# MCU_A_ESP32-WROOM-32U.net
KiCad netlist of a schematic drawn in Altium Designer
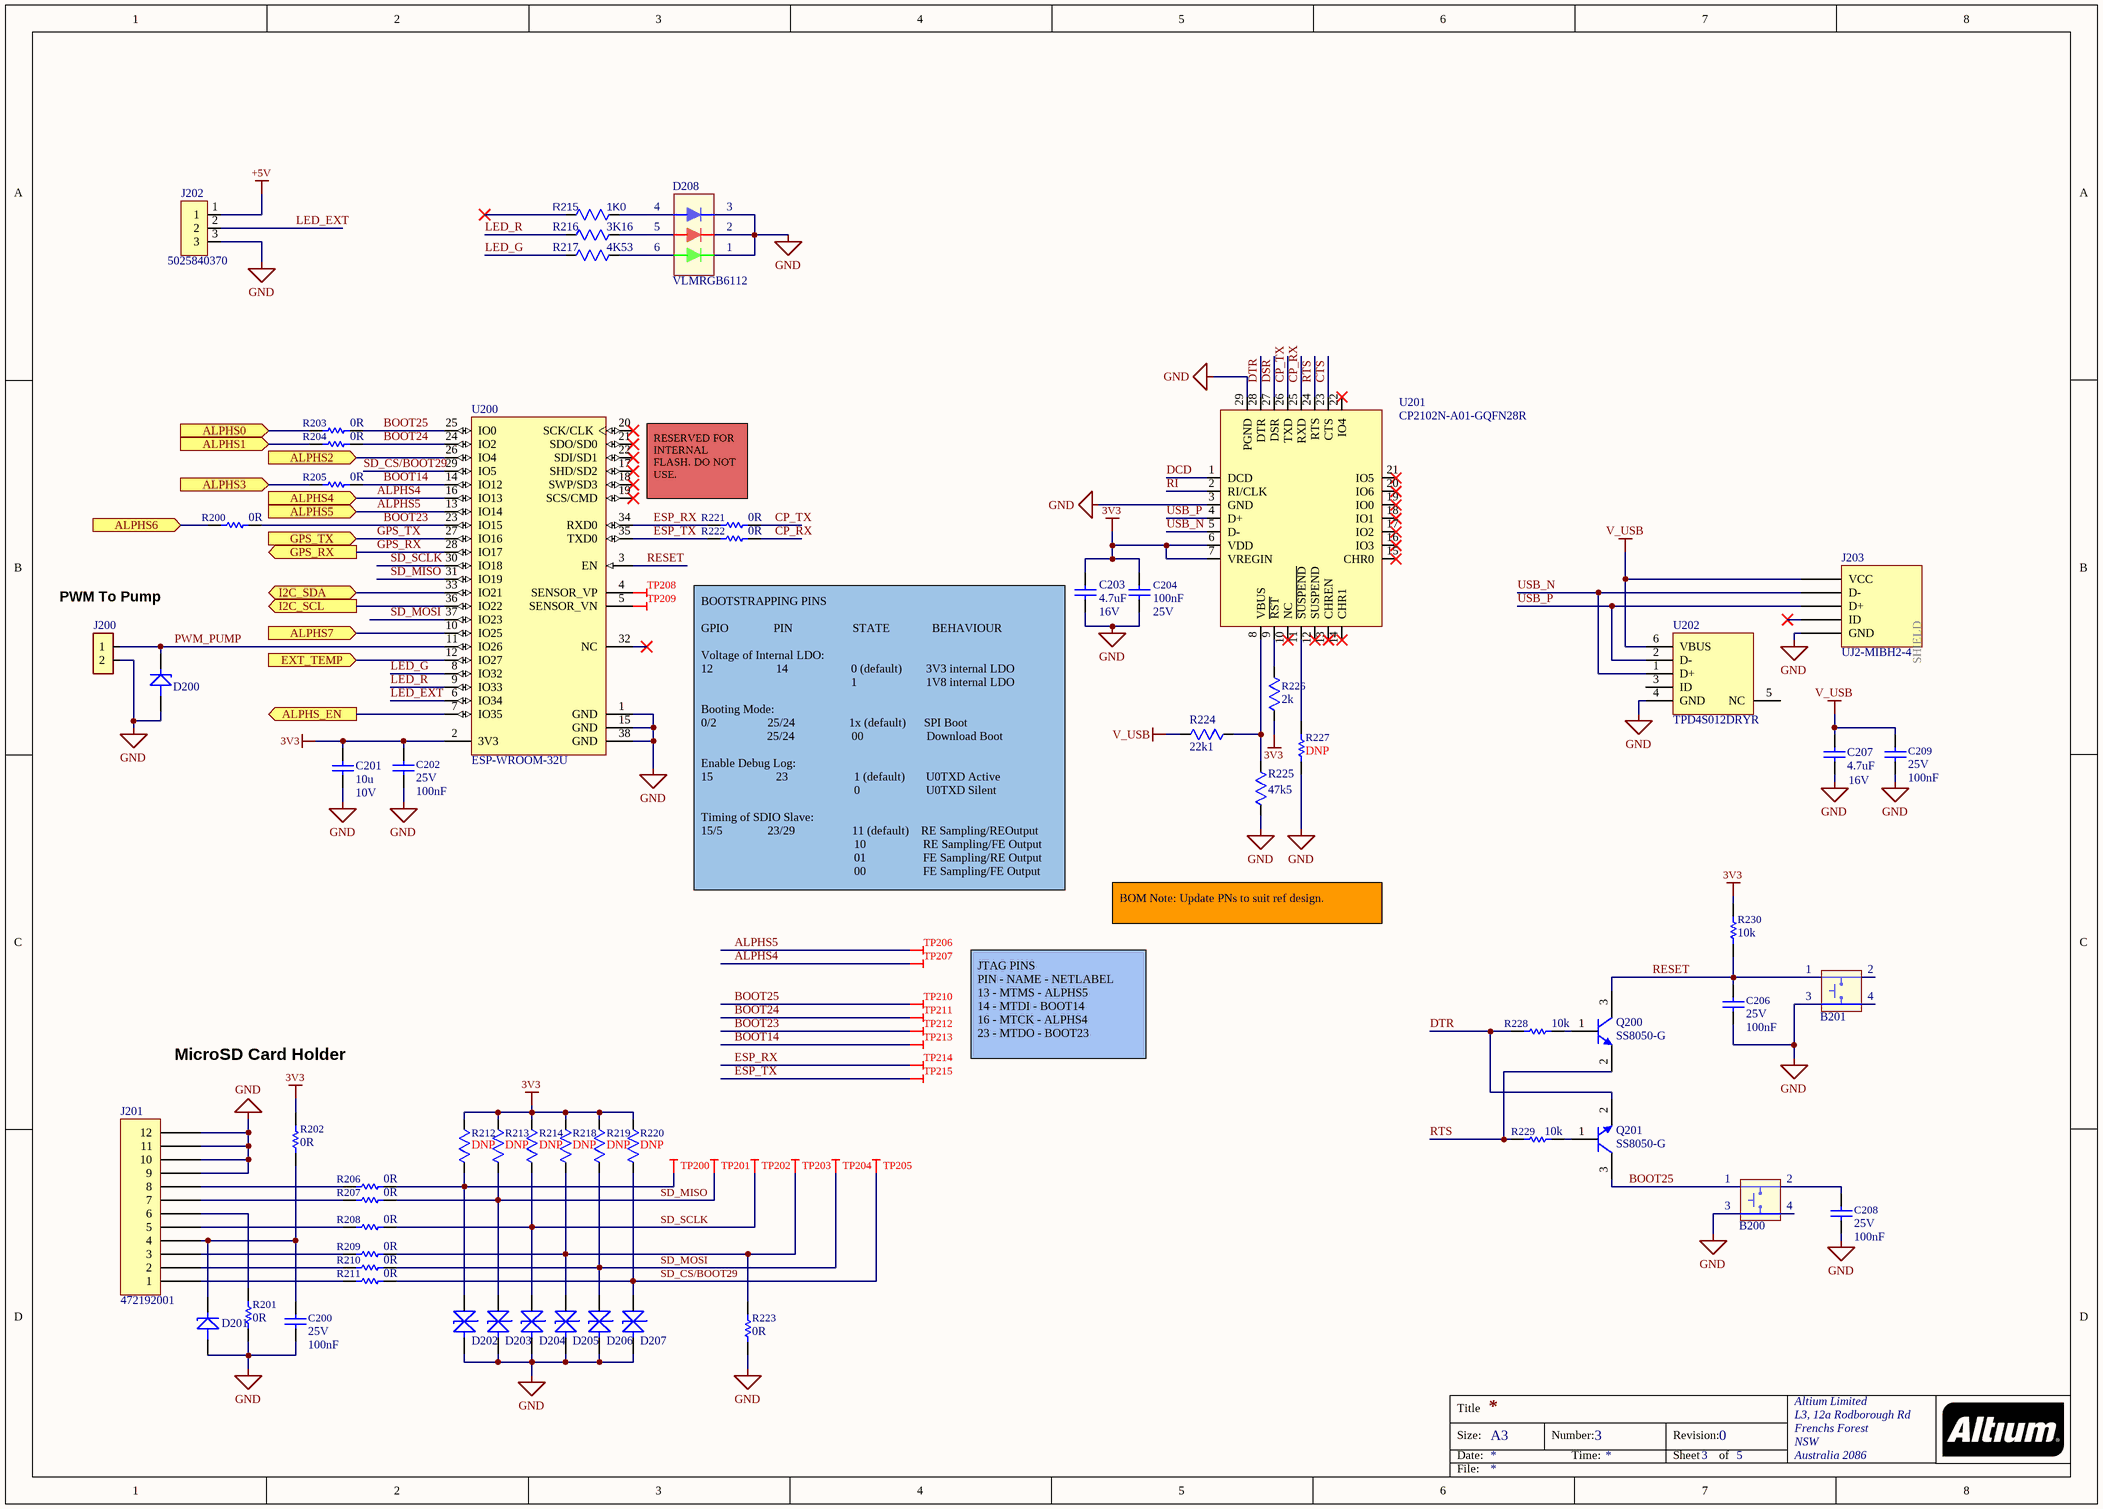
[diagram p0: MCU A ESP32-WROOM-32U.SchDoc]

(export (version "E")
  (design (tool "Eeschema 10.0.6"))
  (components
    (comp (ref "B200")
      (value "Button C&K PTS815 SJG 250 SMTR LFS")
      (footprint "PTS 815")
      (description "Push Button Top")
      (fields
        (field (name "MANUFACTURER") "C&K Components")
        (field (name "MANUFACTURER PART NUMBER") "PTS815 SJG 250 SMTR LFS")
      )
      (libsource (lib "Connectors") (part "Button C&K PTS815 SJG 250 SMTR LFS"))
    )
    (comp (ref "B201")
      (value "Button C&K PTS815 SJG 250 SMTR LFS")
      (footprint "PTS 815")
      (description "Push Button Top")
      (fields
        (field (name "MANUFACTURER") "C&K Components")
        (field (name "MANUFACTURER PART NUMBER") "PTS815 SJG 250 SMTR LFS")
      )
      (libsource (lib "Connectors") (part "Button C&K PTS815 SJG 250 SMTR LFS"))
    )
    (comp (ref "C200")
      (value "100nF")
      (footprint "CAPC1005X06N")
      (fields
        (field (name "VOLTAGE") "25V")
        (field (name "MANUFACTURER PART NUMBER") "CL05A104KA5NNNC")
        (field (name "MANUFACTURER") "Samsung")
        (field (name "Comment") "4.7uF")
      )
      (libsource (lib "Capacitors") (part "4.7uF_0603_10V"))
    )
    (comp (ref "C201")
      (value "10u")
      (footprint "CAPC1005X06N")
      (description "Capacitor")
      (fields
        (field (name "MANUFACTURER PART NUMBER") "CL05A106MP8NUB8")
        (field (name "MANUFACTURER") "Samsung")
        (field (name "VOLTAGE") "10V")
      )
      (libsource (lib "Santuary") (part "CAP{colon} GENERAL"))
    )
    (comp (ref "C202")
      (value "100nF")
      (footprint "CAPC1005X06N")
      (fields
        (field (name "VOLTAGE") "25V")
        (field (name "MANUFACTURER PART NUMBER") "CL05A104KA5NNNC")
        (field (name "MANUFACTURER") "Samsung")
        (field (name "Comment") "4.7uF")
      )
      (libsource (lib "Capacitors") (part "4.7uF_0603_10V"))
    )
    (comp (ref "C203")
      (value "4.7uF")
      (footprint "C1005[0402]")
      (description "Cap,4.7uF,10V,20%,X5R,0402")
      (fields
        (field (name "MANUFACTURER") "Samsung Electro-Mechanics")
        (field (name "MANUFACTURER PART NUMBER") "CL05A475MO5NUNC")
        (field (name "VOLTAGE") "16V")
      )
      (libsource (lib "Capacitors") (part "4.7uF_0402_10V"))
    )
    (comp (ref "C204")
      (value "100nF")
      (footprint "CAPC1005X06N")
      (fields
        (field (name "VOLTAGE") "25V")
        (field (name "MANUFACTURER PART NUMBER") "CL05A104KA5NNNC")
        (field (name "MANUFACTURER") "Samsung")
        (field (name "Comment") "4.7uF")
      )
      (libsource (lib "Capacitors") (part "4.7uF_0603_10V"))
    )
    (comp (ref "C206")
      (value "100nF")
      (footprint "CAPC1005X06N")
      (fields
        (field (name "VOLTAGE") "25V")
        (field (name "MANUFACTURER PART NUMBER") "CL05A104KA5NNNC")
        (field (name "MANUFACTURER") "Samsung")
        (field (name "Comment") "4.7uF")
      )
      (libsource (lib "Capacitors") (part "4.7uF_0603_10V"))
    )
    (comp (ref "C207")
      (value "4.7uF")
      (footprint "C1005[0402]")
      (description "Cap,4.7uF,10V,20%,X5R,0402")
      (fields
        (field (name "MANUFACTURER") "Samsung Electro-Mechanics")
        (field (name "MANUFACTURER PART NUMBER") "CL05A475MO5NUNC")
        (field (name "VOLTAGE") "16V")
      )
      (libsource (lib "Capacitors") (part "4.7uF_0402_10V"))
    )
    (comp (ref "C208")
      (value "100nF")
      (footprint "CAPC1005X06N")
      (fields
        (field (name "VOLTAGE") "25V")
        (field (name "MANUFACTURER PART NUMBER") "CL05A104KA5NNNC")
        (field (name "MANUFACTURER") "Samsung")
        (field (name "Comment") "4.7uF")
      )
      (libsource (lib "Capacitors") (part "4.7uF_0603_10V"))
    )
    (comp (ref "C209")
      (value "100nF")
      (footprint "CAPC1005X06N")
      (fields
        (field (name "VOLTAGE") "25V")
        (field (name "MANUFACTURER PART NUMBER") "CL05A104KA5NNNC")
        (field (name "MANUFACTURER") "Samsung")
        (field (name "Comment") "4.7uF")
      )
      (libsource (lib "Capacitors") (part "4.7uF_0603_10V"))
    )
    (comp (ref "D200")
      (value "3.3V TVS")
      (footprint "NXP PTVSxS1UR-Series (SOD123W)")
      (fields
        (field (name "MANUFACTURER") "Nexperia")
        (field (name "MANUFACTURER PART NUMBER") "PTVS3V3S1UTR,115")
      )
      (libsource (lib "FSM_2018") (part "NXP PTVSxS1UR-Series"))
    )
    (comp (ref "D201")
      (value "3.3V TVS")
      (footprint "NXP PTVSxS1UR-Series (SOD123W)")
      (fields
        (field (name "MANUFACTURER") "Nexperia")
        (field (name "MANUFACTURER PART NUMBER") "PTVS3V3S1UTR,115")
      )
      (libsource (lib "FSM_2018") (part "NXP PTVSxS1UR-Series"))
    )
    (comp (ref "D202")
      (value "ESD7951ST5GOSCT-ND")
      (footprint "SODFL100X40-2N")
      (description "TVS Diode")
      (fields
        (field (name "MANUFACTURER PART NUMBER") "ESD7951ST5G")
        (field (name "MANUFACTURER") "ON Semiconductor")
      )
      (libsource (lib "Gas Monitor Components") (part "ESD7951S"))
    )
    (comp (ref "D203")
      (value "ESD7951ST5GOSCT-ND")
      (footprint "SODFL100X40-2N")
      (description "TVS Diode")
      (fields
        (field (name "MANUFACTURER PART NUMBER") "ESD7951ST5G")
        (field (name "MANUFACTURER") "ON Semiconductor")
      )
      (libsource (lib "Gas Monitor Components") (part "ESD7951S"))
    )
    (comp (ref "D204")
      (value "ESD7951ST5GOSCT-ND")
      (footprint "SODFL100X40-2N")
      (description "TVS Diode")
      (fields
        (field (name "MANUFACTURER PART NUMBER") "ESD7951ST5G")
        (field (name "MANUFACTURER") "ON Semiconductor")
      )
      (libsource (lib "Gas Monitor Components") (part "ESD7951S"))
    )
    (comp (ref "D205")
      (value "ESD7951ST5GOSCT-ND")
      (footprint "SODFL100X40-2N")
      (description "TVS Diode")
      (fields
        (field (name "MANUFACTURER PART NUMBER") "ESD7951ST5G")
        (field (name "MANUFACTURER") "ON Semiconductor")
      )
      (libsource (lib "Gas Monitor Components") (part "ESD7951S"))
    )
    (comp (ref "D206")
      (value "ESD7951ST5GOSCT-ND")
      (footprint "SODFL100X40-2N")
      (description "TVS Diode")
      (fields
        (field (name "MANUFACTURER PART NUMBER") "ESD7951ST5G")
        (field (name "MANUFACTURER") "ON Semiconductor")
      )
      (libsource (lib "Gas Monitor Components") (part "ESD7951S"))
    )
    (comp (ref "D207")
      (value "ESD7951ST5GOSCT-ND")
      (footprint "SODFL100X40-2N")
      (description "TVS Diode")
      (fields
        (field (name "MANUFACTURER PART NUMBER") "ESD7951ST5G")
        (field (name "MANUFACTURER") "ON Semiconductor")
      )
      (libsource (lib "Gas Monitor Components") (part "ESD7951S"))
    )
    (comp (ref "D208")
      (value "VLMRGB6112")
      (footprint "VLMRGB6112")
      (description "LED RGB Clear 624nm/526nm/469nm 2V/3.1V/3V PLCC-6")
      (fields
        (field (name "MANUFACTURER") "Vishay Semiconductor Opto Division")
        (field (name "MANUFACTURER PART NUMBER") "VLMRGB6112-00-GS08")
      )
      (libsource (lib "LEDs") (part "VLMRGB6112"))
    )
    (comp (ref "J200")
      (value "PWM To Pump")
      (footprint "6410/2pin")
      (description "Connector 2 pin")
      (fields (field (name "MANUFACTURER") "Molex") (field (name "MANUFACTURER PART NUMBER") "0022232023"))
      (libsource (lib "VolcDB") (part "CON2"))
    )
    (comp (ref "J201")
      (value "472192001")
      (footprint "SD-47219-001")
      (fields (field (name "MANUFACTURER") "Molex") (field (name "MANUFACTURER PART NUMBER") "0472192001"))
      (libsource (lib "Gas Monitor Components") (part "CON12"))
    )
    (comp (ref "J202")
      (value "5025840370")
      (footprint "502584-0370")
      (fields (field (name "MANUFACTURER") "Molex"))
      (libsource (lib "Sora") (part "CONN{colon} 3x1"))
    )
    (comp (ref "J203")
      (value "UJ2-MIBH2-4")
      (footprint "UJ2-MIBH2-4-SMT")
      (fields
        (field (name "MANUFACTURER") "CUI")
        (field (name "MANUFACTURER PART NUMBER") "UJ2-MIBH2-4-SMT-TR")
      )
      (libsource (lib "Gas Monitor Components") (part "USB Shield"))
    )
    (comp (ref "Q200")
      (value "SS8050-G")
      (footprint "ONSC-SOT-23-3-318-08_V")
      (description "General Purpose Transistor, NPN Silicon, 3-Pin SOT-23, Tape and Reel")
      (fields (field (name "MANUFACTURER") "Comchip Technology"))
      (libsource (lib "Altium Content Vault") (part "ONSC-NPN-B1E2C3-3"))
    )
    (comp (ref "Q201")
      (value "SS8050-G")
      (footprint "ONSC-SOT-23-3-318-08_V")
      (description "General Purpose Transistor, NPN Silicon, 3-Pin SOT-23, Tape and Reel")
      (fields (field (name "MANUFACTURER") "Comchip Technology"))
      (libsource (lib "Altium Content Vault") (part "ONSC-NPN-B1E2C3-3"))
    )
    (comp (ref "R200")
      (value "0R")
      (footprint "RESC1005X03N")
      (fields
        (field (name "MANUFACTURER") "Panasonic")
        (field (name "MANUFACTURER PART NUMBER") "ERJ-2GE0R00X")
        (field (name "Comment") "RES: GENERAL")
      )
      (libsource (lib "Santuary") (part "RES{colon} GENERAL"))
    )
    (comp (ref "R201")
      (value "0R")
      (footprint "RESC1005X03N")
      (fields
        (field (name "MANUFACTURER") "Panasonic")
        (field (name "MANUFACTURER PART NUMBER") "ERJ-2GE0R00X")
        (field (name "Comment") "RES: GENERAL")
      )
      (libsource (lib "Santuary") (part "RES{colon} GENERAL"))
    )
    (comp (ref "R202")
      (value "0R")
      (footprint "RESC1005X03N")
      (fields
        (field (name "MANUFACTURER") "Panasonic")
        (field (name "MANUFACTURER PART NUMBER") "ERJ-2GE0R00X")
        (field (name "Comment") "RES: GENERAL")
      )
      (libsource (lib "Santuary") (part "RES{colon} GENERAL"))
    )
    (comp (ref "R203")
      (value "0R")
      (footprint "RESC1005X03N")
      (fields
        (field (name "MANUFACTURER") "Panasonic")
        (field (name "MANUFACTURER PART NUMBER") "ERJ-2GE0R00X")
        (field (name "Comment") "RES: GENERAL")
      )
      (libsource (lib "Santuary") (part "RES{colon} GENERAL"))
    )
    (comp (ref "R204")
      (value "0R")
      (footprint "RESC1005X03N")
      (fields
        (field (name "MANUFACTURER") "Panasonic")
        (field (name "MANUFACTURER PART NUMBER") "ERJ-2GE0R00X")
        (field (name "Comment") "RES: GENERAL")
      )
      (libsource (lib "Santuary") (part "RES{colon} GENERAL"))
    )
    (comp (ref "R205")
      (value "0R")
      (footprint "RESC1005X03N")
      (fields
        (field (name "MANUFACTURER") "Panasonic")
        (field (name "MANUFACTURER PART NUMBER") "ERJ-2GE0R00X")
        (field (name "Comment") "RES: GENERAL")
      )
      (libsource (lib "Santuary") (part "RES{colon} GENERAL"))
    )
    (comp (ref "R206")
      (value "0R")
      (footprint "RESC1005X03N")
      (fields
        (field (name "MANUFACTURER") "Panasonic")
        (field (name "MANUFACTURER PART NUMBER") "ERJ-2GE0R00X")
        (field (name "Comment") "RES: GENERAL")
      )
      (libsource (lib "Santuary") (part "RES{colon} GENERAL"))
    )
    (comp (ref "R207")
      (value "0R")
      (footprint "RESC1005X03N")
      (fields
        (field (name "MANUFACTURER") "Panasonic")
        (field (name "MANUFACTURER PART NUMBER") "ERJ-2GE0R00X")
        (field (name "Comment") "RES: GENERAL")
      )
      (libsource (lib "Santuary") (part "RES{colon} GENERAL"))
    )
    (comp (ref "R208")
      (value "0R")
      (footprint "RESC1005X03N")
      (fields
        (field (name "MANUFACTURER") "Panasonic")
        (field (name "MANUFACTURER PART NUMBER") "ERJ-2GE0R00X")
        (field (name "Comment") "RES: GENERAL")
      )
      (libsource (lib "Santuary") (part "RES{colon} GENERAL"))
    )
    (comp (ref "R209")
      (value "0R")
      (footprint "RESC1005X03N")
      (fields
        (field (name "MANUFACTURER") "Panasonic")
        (field (name "MANUFACTURER PART NUMBER") "ERJ-2GE0R00X")
        (field (name "Comment") "RES: GENERAL")
      )
      (libsource (lib "Santuary") (part "RES{colon} GENERAL"))
    )
    (comp (ref "R210")
      (value "0R")
      (footprint "RESC1005X03N")
      (fields
        (field (name "MANUFACTURER") "Panasonic")
        (field (name "MANUFACTURER PART NUMBER") "ERJ-2GE0R00X")
        (field (name "Comment") "RES: GENERAL")
      )
      (libsource (lib "Santuary") (part "RES{colon} GENERAL"))
    )
    (comp (ref "R211")
      (value "0R")
      (footprint "RESC1005X03N")
      (fields
        (field (name "MANUFACTURER") "Panasonic")
        (field (name "MANUFACTURER PART NUMBER") "ERJ-2GE0R00X")
        (field (name "Comment") "RES: GENERAL")
      )
      (libsource (lib "Santuary") (part "RES{colon} GENERAL"))
    )
    (comp (ref "R212")
      (value "DNP")
      (footprint "RESC1005X03N")
      (description "RES 1K Ohm ±5%, 0.25W,1/4W 0603")
      (fields (field (name "Comment") "10K"))
      (libsource (lib "Resistors") (part "1K00_0603_0.1W"))
    )
    (comp (ref "R213")
      (value "DNP")
      (footprint "RESC1005X03N")
      (description "RES 1K Ohm ±5%, 0.25W,1/4W 0603")
      (fields (field (name "Comment") "10K"))
      (libsource (lib "Resistors") (part "1K00_0603_0.1W"))
    )
    (comp (ref "R214")
      (value "DNP")
      (footprint "RESC1005X03N")
      (description "RES 1K Ohm ±5%, 0.25W,1/4W 0603")
      (fields (field (name "Comment") "10K"))
      (libsource (lib "Resistors") (part "1K00_0603_0.1W"))
    )
    (comp (ref "R215")
      (value "1K0")
      (footprint "R1608[0603] small")
      (description "RES 1K Ohm ±5%, 0.25W,1/4W 0603")
      (fields (field (name "MANUFACTURER") "Rohm") (field (name "MANUFACTURER PART NUMBER") "ESR03EZPJ102"))
      (libsource (lib "Resistors") (part "1K00_0603_0.1W"))
    )
    (comp (ref "R216")
      (value "3K16")
      (footprint "R1608[0603] small")
      (description "Res,SMD,1/10W,3K16,0603,1%")
      (fields
        (field (name "MANUFACTURER") "Stackpole Electronics")
        (field (name "MANUFACTURER PART NUMBER") "RMCF0603FT3K16")
      )
      (libsource (lib "Resistors") (part "3K16_Resistor_0603"))
    )
    (comp (ref "R217")
      (value "4K53")
      (footprint "R1608[0603] small")
      (description "Res,SMD,4K53,1/10W,1%,0603")
      (fields
        (field (name "MANUFACTURER") "Yageo")
        (field (name "MANUFACTURER PART NUMBER") "RC0603FR-074K53L")
      )
      (libsource (lib "Resistors") (part "4K53_Resistor_0603"))
    )
    (comp (ref "R218")
      (value "DNP")
      (footprint "RESC1005X03N")
      (description "RES 1K Ohm ±5%, 0.25W,1/4W 0603")
      (fields (field (name "Comment") "10K"))
      (libsource (lib "Resistors") (part "1K00_0603_0.1W"))
    )
    (comp (ref "R219")
      (value "DNP")
      (footprint "RESC1005X03N")
      (description "RES 1K Ohm ±5%, 0.25W,1/4W 0603")
      (fields (field (name "Comment") "10K"))
      (libsource (lib "Resistors") (part "1K00_0603_0.1W"))
    )
    (comp (ref "R220")
      (value "DNP")
      (footprint "RESC1005X03N")
      (description "RES 1K Ohm ±5%, 0.25W,1/4W 0603")
      (fields (field (name "Comment") "10K"))
      (libsource (lib "Resistors") (part "1K00_0603_0.1W"))
    )
    (comp (ref "R221")
      (value "0R")
      (footprint "RESC1005X03N")
      (fields
        (field (name "MANUFACTURER") "Panasonic")
        (field (name "MANUFACTURER PART NUMBER") "ERJ-2GE0R00X")
        (field (name "Comment") "RES: GENERAL")
      )
      (libsource (lib "Santuary") (part "RES{colon} GENERAL"))
    )
    (comp (ref "R222")
      (value "0R")
      (footprint "RESC1005X03N")
      (fields
        (field (name "MANUFACTURER") "Panasonic")
        (field (name "MANUFACTURER PART NUMBER") "ERJ-2GE0R00X")
        (field (name "Comment") "RES: GENERAL")
      )
      (libsource (lib "Santuary") (part "RES{colon} GENERAL"))
    )
    (comp (ref "R223")
      (value "0R")
      (footprint "RESC1005X03N")
      (fields
        (field (name "MANUFACTURER") "Panasonic")
        (field (name "MANUFACTURER PART NUMBER") "ERJ-2GE0R00X")
        (field (name "Comment") "RES: GENERAL")
      )
      (libsource (lib "Santuary") (part "RES{colon} GENERAL"))
    )
    (comp (ref "R224")
      (value "22k1")
      (footprint "R1005[0402]")
      (description "Res,SMD,22k,0603,5%,1/4W")
      (fields
        (field (name "MANUFACTURER PART NUMBER") "ERJ-2RKF2212X")
        (field (name "MANUFACTURER") "Panasonic")
      )
      (libsource (lib "Resistors") (part "22K_0603_1/4W"))
    )
    (comp (ref "R225")
      (value "47k5")
      (footprint "R1005[0402]")
      (description "Res,SMD,22k,0603,5%,1/4W")
      (fields
        (field (name "MANUFACTURER PART NUMBER") "ERJ-2RKF4752X")
        (field (name "MANUFACTURER") "Panasonic")
      )
      (libsource (lib "Resistors") (part "22K_0603_1/4W"))
    )
    (comp (ref "R226")
      (value "2k")
      (footprint "R1005[0402]")
      (fields
        (field (name "MANUFACTURER") "Panasonic")
        (field (name "MANUFACTURER PART NUMBER") "ERJ-2RKF2001X")
        (field (name "Comment") "10K")
      )
      (libsource (lib "Resistors") (part "1K00_0603_0.1W"))
    )
    (comp (ref "R227")
      (value "DNP")
      (footprint "RESC1005X03N")
      (fields (field (name "Comment") "RES: GENERAL"))
      (libsource (lib "Santuary") (part "RES{colon} GENERAL"))
    )
    (comp (ref "R228")
      (value "10k")
      (footprint "RESC1005X03N")
      (fields
        (field (name "MANUFACTURER") "Panasonic")
        (field (name "MANUFACTURER PART NUMBER") "ERJ-2RKF1002X")
        (field (name "Comment") "RES: GENERAL")
      )
      (libsource (lib "Santuary") (part "RES{colon} GENERAL"))
    )
    (comp (ref "R229")
      (value "10k")
      (footprint "RESC1005X03N")
      (fields
        (field (name "MANUFACTURER") "Panasonic")
        (field (name "MANUFACTURER PART NUMBER") "ERJ-2RKF1002X")
        (field (name "Comment") "RES: GENERAL")
      )
      (libsource (lib "Santuary") (part "RES{colon} GENERAL"))
    )
    (comp (ref "R230")
      (value "10k")
      (footprint "RESC1005X03N")
      (fields
        (field (name "MANUFACTURER") "Panasonic")
        (field (name "MANUFACTURER PART NUMBER") "ERJ-2RKF1002X")
        (field (name "Comment") "RES: GENERAL")
      )
      (libsource (lib "Santuary") (part "RES{colon} GENERAL"))
    )
    (comp (ref "TP200")
      (value "PAD")
      (footprint "TP_SMD_39MIL")
      (description "SMD Test Pad")
      (fields (field (name "MANUFACTURER") "No P/N Required"))
      (libsource (lib "Connectors") (part "TP_SMD_39MIL"))
    )
    (comp (ref "TP201")
      (value "PAD")
      (footprint "TP_SMD_39MIL")
      (description "SMD Test Pad")
      (fields (field (name "MANUFACTURER") "No P/N Required"))
      (libsource (lib "Connectors") (part "TP_SMD_39MIL"))
    )
    (comp (ref "TP202")
      (value "PAD")
      (footprint "TP_SMD_39MIL")
      (description "SMD Test Pad")
      (fields (field (name "MANUFACTURER") "No P/N Required"))
      (libsource (lib "Connectors") (part "TP_SMD_39MIL"))
    )
    (comp (ref "TP203")
      (value "PAD")
      (footprint "TP_SMD_39MIL")
      (description "SMD Test Pad")
      (fields (field (name "MANUFACTURER") "No P/N Required"))
      (libsource (lib "Connectors") (part "TP_SMD_39MIL"))
    )
    (comp (ref "TP204")
      (value "PAD")
      (footprint "TP_SMD_39MIL")
      (description "SMD Test Pad")
      (fields (field (name "MANUFACTURER") "No P/N Required"))
      (libsource (lib "Connectors") (part "TP_SMD_39MIL"))
    )
    (comp (ref "TP205")
      (value "PAD")
      (footprint "TP_SMD_39MIL")
      (description "SMD Test Pad")
      (fields (field (name "MANUFACTURER") "No P/N Required"))
      (libsource (lib "Connectors") (part "TP_SMD_39MIL"))
    )
    (comp (ref "TP206")
      (value "PAD")
      (footprint "TP_SMD_39MIL")
      (description "SMD Test Pad")
      (fields (field (name "MANUFACTURER") "No P/N Required"))
      (libsource (lib "Connectors") (part "TP_SMD_39MIL"))
    )
    (comp (ref "TP207")
      (value "PAD")
      (footprint "TP_SMD_39MIL")
      (description "SMD Test Pad")
      (fields (field (name "MANUFACTURER") "No P/N Required"))
      (libsource (lib "Connectors") (part "TP_SMD_39MIL"))
    )
    (comp (ref "TP208")
      (value "PAD")
      (footprint "TP_SMD_39MIL")
      (description "SMD Test Pad")
      (fields (field (name "MANUFACTURER") "No P/N Required"))
      (libsource (lib "Connectors") (part "TP_SMD_39MIL"))
    )
    (comp (ref "TP209")
      (value "PAD")
      (footprint "TP_SMD_39MIL")
      (description "SMD Test Pad")
      (fields (field (name "MANUFACTURER") "No P/N Required"))
      (libsource (lib "Connectors") (part "TP_SMD_39MIL"))
    )
    (comp (ref "TP210")
      (value "PAD")
      (footprint "TP_SMD_39MIL")
      (description "SMD Test Pad")
      (fields (field (name "MANUFACTURER") "No P/N Required"))
      (libsource (lib "Connectors") (part "TP_SMD_39MIL"))
    )
    (comp (ref "TP211")
      (value "PAD")
      (footprint "TP_SMD_39MIL")
      (description "SMD Test Pad")
      (fields (field (name "MANUFACTURER") "No P/N Required"))
      (libsource (lib "Connectors") (part "TP_SMD_39MIL"))
    )
    (comp (ref "TP212")
      (value "PAD")
      (footprint "TP_SMD_39MIL")
      (description "SMD Test Pad")
      (fields (field (name "MANUFACTURER") "No P/N Required"))
      (libsource (lib "Connectors") (part "TP_SMD_39MIL"))
    )
    (comp (ref "TP213")
      (value "PAD")
      (footprint "TP_SMD_39MIL")
      (description "SMD Test Pad")
      (fields (field (name "MANUFACTURER") "No P/N Required"))
      (libsource (lib "Connectors") (part "TP_SMD_39MIL"))
    )
    (comp (ref "TP214")
      (value "PAD")
      (footprint "TP_SMD_39MIL")
      (description "SMD Test Pad")
      (fields (field (name "MANUFACTURER") "No P/N Required"))
      (libsource (lib "Connectors") (part "TP_SMD_39MIL"))
    )
    (comp (ref "TP215")
      (value "PAD")
      (footprint "TP_SMD_39MIL")
      (description "SMD Test Pad")
      (fields (field (name "MANUFACTURER") "No P/N Required"))
      (libsource (lib "Connectors") (part "TP_SMD_39MIL"))
    )
    (comp (ref "U200")
      (value "ESP-WROOM-32U")
      (footprint "OLMX-ESP-WROOM-32")
      (description "Espressif System, 2.7 to 3.6 V, -40 to 85 degC, 38-Pin SMD")
      (fields
        (field (name "MANUFACTURER") "Espressif Systems")
        (field (name "MANUFACTURER PART NUMBER") "ESP32-WROOM-32U")
      )
      (libsource (lib "Altium Content Vault") (part "OLMX-ESP-WROOM-32-38"))
    )
    (comp (ref "U201")
      (value "CP2102N-A01-GQFN28R")
      (footprint "QFN50P500X500X80_HS-29N")
      (description "USB to UART converter")
      (fields (field (name "MANUFACTURER") "Silicon Labs"))
      (libsource (lib "ICs-V") (part "CP2102N QFN28"))
    )
    (comp (ref "U202")
      (value "TPD4S012DRYR")
      (footprint "DRY0006A")
      (fields (field (name "MANUFACTURER") "Texas Instruments"))
      (libsource (lib "Altium Content Vault") (part "TI-TPD4S012-SON_DRY-6"))
    )
  )
  (nets
    (net (code "1") (name "+5V") (class "Default")
      (node (ref "J202") (pin "1") (pinfunction "1_1") (pintype "passive"))
    )
    (net (code "2") (name "/ALPHS0") (class "Default")
      (node (ref "R203") (pin "2") (pinfunction "2_2") (pintype "passive"))
    )
    (net (code "3") (name "/ALPHS1") (class "Default")
      (node (ref "R204") (pin "2") (pinfunction "2_2") (pintype "passive"))
    )
    (net (code "4") (name "/ALPHS2") (class "Default")
      (node (ref "U200") (pin "26") (pinfunction "IO4_26") (pintype "bidirectional"))
    )
    (net (code "5") (name "/ALPHS3") (class "Default")
      (node (ref "R205") (pin "2") (pinfunction "2_2") (pintype "passive"))
    )
    (net (code "6") (name "/ALPHS4") (class "Default")
      (node (ref "TP207") (pin "1") (pintype "passive"))
      (node (ref "U200") (pin "16") (pinfunction "IO13_16") (pintype "bidirectional"))
    )
    (net (code "7") (name "/ALPHS5") (class "Default")
      (node (ref "TP206") (pin "1") (pintype "passive"))
      (node (ref "U200") (pin "13") (pinfunction "IO14_13") (pintype "bidirectional"))
    )
    (net (code "8") (name "/ALPHS6") (class "Default")
      (node (ref "R200") (pin "2") (pinfunction "2_2") (pintype "passive"))
    )
    (net (code "9") (name "/ALPHS7") (class "Default")
      (node (ref "U200") (pin "10") (pinfunction "IO25_10") (pintype "bidirectional"))
    )
    (net (code "10") (name "/ALPHS_EN") (class "Default")
      (node (ref "U200") (pin "7") (pinfunction "IO35_7") (pintype "bidirectional"))
    )
    (net (code "11") (name "/BOOT14") (class "Default")
      (node (ref "R205") (pin "1") (pinfunction "1_1") (pintype "passive"))
      (node (ref "TP213") (pin "1") (pintype "passive"))
      (node (ref "U200") (pin "14") (pinfunction "IO12_14") (pintype "bidirectional"))
    )
    (net (code "12") (name "/BOOT23") (class "Default")
      (node (ref "R200") (pin "1") (pinfunction "1_1") (pintype "passive"))
      (node (ref "TP212") (pin "1") (pintype "passive"))
      (node (ref "U200") (pin "23") (pinfunction "IO15_23") (pintype "bidirectional"))
    )
    (net (code "13") (name "/BOOT24") (class "Default")
      (node (ref "R204") (pin "1") (pinfunction "1_1") (pintype "passive"))
      (node (ref "TP211") (pin "1") (pintype "passive"))
      (node (ref "U200") (pin "24") (pinfunction "IO2_24") (pintype "bidirectional"))
    )
    (net (code "14") (name "/BOOT25") (class "Default")
      (node (ref "B200") (pin "1") (pinfunction "1_1") (pintype "passive"))
      (node (ref "Q201") (pin "3") (pinfunction "C_3") (pintype "passive"))
      (node (ref "R203") (pin "1") (pinfunction "1_1") (pintype "passive"))
      (node (ref "TP210") (pin "1") (pintype "passive"))
      (node (ref "U200") (pin "25") (pinfunction "IO0_25") (pintype "bidirectional"))
    )
    (net (code "15") (name "/CP_RX") (class "Default")
      (node (ref "R222") (pin "1") (pinfunction "1_1") (pintype "passive"))
      (node (ref "U201") (pin "25") (pinfunction "RXD_25") (pintype "passive"))
    )
    (net (code "16") (name "/CP_TX") (class "Default")
      (node (ref "R221") (pin "1") (pinfunction "1_1") (pintype "passive"))
      (node (ref "U201") (pin "26") (pinfunction "TXD_26") (pintype "passive"))
    )
    (net (code "17") (name "/CTS") (class "Default")
      (node (ref "U201") (pin "23") (pinfunction "CTS_23") (pintype "passive"))
    )
    (net (code "18") (name "/DCD") (class "Default")
      (node (ref "U201") (pin "1") (pinfunction "DCD_1") (pintype "passive"))
    )
    (net (code "19") (name "/DSR") (class "Default")
      (node (ref "U201") (pin "27") (pinfunction "DSR_27") (pintype "passive"))
    )
    (net (code "20") (name "/DTR") (class "Default")
      (node (ref "Q201") (pin "2") (pinfunction "E_2") (pintype "passive"))
      (node (ref "R228") (pin "2") (pinfunction "2_2") (pintype "passive"))
      (node (ref "U201") (pin "28") (pinfunction "DTR_28") (pintype "passive"))
    )
    (net (code "21") (name "/ESP_RX") (class "Default")
      (node (ref "R221") (pin "2") (pinfunction "2_2") (pintype "passive"))
      (node (ref "TP214") (pin "1") (pintype "passive"))
      (node (ref "U200") (pin "34") (pinfunction "RXD0_34") (pintype "bidirectional"))
    )
    (net (code "22") (name "/ESP_TX") (class "Default")
      (node (ref "R222") (pin "2") (pinfunction "2_2") (pintype "passive"))
      (node (ref "TP215") (pin "1") (pintype "passive"))
      (node (ref "U200") (pin "35") (pinfunction "TXD0_35") (pintype "bidirectional"))
    )
    (net (code "23") (name "/EXT_TEMP") (class "Default")
      (node (ref "U200") (pin "12") (pinfunction "IO27_12") (pintype "bidirectional"))
    )
    (net (code "24") (name "/GPS_RX") (class "Default")
      (node (ref "U200") (pin "28") (pinfunction "IO17_28") (pintype "bidirectional"))
    )
    (net (code "25") (name "/GPS_TX") (class "Default")
      (node (ref "U200") (pin "27") (pinfunction "IO16_27") (pintype "bidirectional"))
    )
    (net (code "26") (name "/I2C_SCL") (class "Default")
      (node (ref "U200") (pin "36") (pinfunction "IO22_36") (pintype "bidirectional"))
    )
    (net (code "27") (name "/I2C_SDA") (class "Default")
      (node (ref "U200") (pin "33") (pinfunction "IO21_33") (pintype "bidirectional"))
    )
    (net (code "28") (name "/LED_EXT") (class "Default")
      (node (ref "J202") (pin "2") (pinfunction "2_2") (pintype "passive"))
      (node (ref "U200") (pin "6") (pinfunction "IO34_6") (pintype "bidirectional"))
    )
    (net (code "29") (name "/LED_G") (class "Default")
      (node (ref "R217") (pin "1") (pintype "passive"))
      (node (ref "U200") (pin "8") (pinfunction "IO32_8") (pintype "bidirectional"))
    )
    (net (code "30") (name "/LED_R") (class "Default")
      (node (ref "R216") (pin "1") (pintype "passive"))
      (node (ref "U200") (pin "9") (pinfunction "IO33_9") (pintype "bidirectional"))
    )
    (net (code "31") (name "/PWM_PUMP") (class "Default")
      (node (ref "D200") (pin "1") (pinfunction "1_1") (pintype "passive"))
      (node (ref "J200") (pin "1") (pinfunction "1_1") (pintype "passive"))
      (node (ref "U200") (pin "11") (pinfunction "IO26_11") (pintype "bidirectional"))
    )
    (net (code "32") (name "/RESET") (class "Default")
      (node (ref "B201") (pin "1") (pinfunction "1_1") (pintype "passive"))
      (node (ref "C206") (pin "1") (pintype "passive"))
      (node (ref "Q200") (pin "3") (pinfunction "C_3") (pintype "passive"))
      (node (ref "R230") (pin "2") (pinfunction "2_2") (pintype "passive"))
      (node (ref "U200") (pin "3") (pinfunction "EN_3") (pintype "input"))
    )
    (net (code "33") (name "/RI") (class "Default")
      (node (ref "U201") (pin "2") (pinfunction "RI/CLK_2") (pintype "passive"))
    )
    (net (code "34") (name "/RTS") (class "Default")
      (node (ref "Q200") (pin "2") (pinfunction "E_2") (pintype "passive"))
      (node (ref "R229") (pin "2") (pinfunction "2_2") (pintype "passive"))
      (node (ref "U201") (pin "24") (pinfunction "RTS_24") (pintype "passive"))
    )
    (net (code "35") (name "/SD_CS{slash}BOOT29") (class "Default")
      (node (ref "D207") (pin "2") (pinfunction "ANODE_2") (pintype "passive"))
      (node (ref "R211") (pin "1") (pinfunction "1_1") (pintype "passive"))
      (node (ref "R220") (pin "1") (pintype "passive"))
      (node (ref "TP205") (pin "1") (pintype "passive"))
      (node (ref "U200") (pin "29") (pinfunction "IO5_29") (pintype "bidirectional"))
    )
    (net (code "36") (name "/SD_MISO") (class "Default")
      (node (ref "D203") (pin "2") (pinfunction "ANODE_2") (pintype "passive"))
      (node (ref "R207") (pin "1") (pinfunction "1_1") (pintype "passive"))
      (node (ref "R213") (pin "1") (pintype "passive"))
      (node (ref "TP201") (pin "1") (pintype "passive"))
      (node (ref "U200") (pin "31") (pinfunction "IO19_31") (pintype "bidirectional"))
    )
    (net (code "37") (name "/SD_MOSI") (class "Default")
      (node (ref "D206") (pin "2") (pinfunction "ANODE_2") (pintype "passive"))
      (node (ref "R210") (pin "1") (pinfunction "1_1") (pintype "passive"))
      (node (ref "R219") (pin "1") (pintype "passive"))
      (node (ref "TP204") (pin "1") (pintype "passive"))
      (node (ref "U200") (pin "37") (pinfunction "IO23_37") (pintype "bidirectional"))
    )
    (net (code "38") (name "/SD_SCLK") (class "Default")
      (node (ref "D204") (pin "2") (pinfunction "ANODE_2") (pintype "passive"))
      (node (ref "R208") (pin "1") (pinfunction "1_1") (pintype "passive"))
      (node (ref "R214") (pin "1") (pintype "passive"))
      (node (ref "TP202") (pin "1") (pintype "passive"))
      (node (ref "U200") (pin "30") (pinfunction "IO18_30") (pintype "bidirectional"))
    )
    (net (code "39") (name "/USB_N") (class "Default")
      (node (ref "J203") (pin "2") (pinfunction "D-_2") (pintype "passive"))
      (node (ref "U201") (pin "5") (pinfunction "D-_5") (pintype "passive"))
      (node (ref "U202") (pin "1") (pinfunction "D+_1") (pintype "passive"))
    )
    (net (code "40") (name "/USB_P") (class "Default")
      (node (ref "J203") (pin "3") (pinfunction "D+_3") (pintype "passive"))
      (node (ref "U201") (pin "4") (pinfunction "D+_4") (pintype "passive"))
      (node (ref "U202") (pin "2") (pinfunction "D-_2") (pintype "passive"))
    )
    (net (code "41") (name "3V3") (class "Default")
      (node (ref "C201") (pin "2") (pinfunction "2_2") (pintype "passive"))
      (node (ref "C202") (pin "1") (pintype "passive"))
      (node (ref "C203") (pin "2") (pintype "passive"))
      (node (ref "C204") (pin "1") (pintype "passive"))
      (node (ref "R202") (pin "1") (pinfunction "1_1") (pintype "passive"))
      (node (ref "R212") (pin "2") (pintype "passive"))
      (node (ref "R213") (pin "2") (pintype "passive"))
      (node (ref "R214") (pin "2") (pintype "passive"))
      (node (ref "R218") (pin "2") (pintype "passive"))
      (node (ref "R219") (pin "2") (pintype "passive"))
      (node (ref "R220") (pin "2") (pintype "passive"))
      (node (ref "R226") (pin "1") (pintype "passive"))
      (node (ref "R230") (pin "1") (pinfunction "1_1") (pintype "passive"))
      (node (ref "U200") (pin "2") (pinfunction "3V3_2") (pintype "power_in"))
      (node (ref "U201") (pin "6") (pinfunction "VDD_6") (pintype "power_in"))
      (node (ref "U201") (pin "7") (pinfunction "VREGIN_7") (pintype "power_in"))
    )
    (net (code "42") (name "GND") (class "Default")
      (node (ref "B200") (pin "3") (pinfunction "3_3") (pintype "passive"))
      (node (ref "B201") (pin "3") (pinfunction "3_3") (pintype "passive"))
      (node (ref "C200") (pin "2") (pintype "passive"))
      (node (ref "C201") (pin "1") (pinfunction "1_1") (pintype "passive"))
      (node (ref "C202") (pin "2") (pintype "passive"))
      (node (ref "C203") (pin "1") (pintype "passive"))
      (node (ref "C204") (pin "2") (pintype "passive"))
      (node (ref "C206") (pin "2") (pintype "passive"))
      (node (ref "C207") (pin "1") (pintype "passive"))
      (node (ref "C208") (pin "2") (pintype "passive"))
      (node (ref "C209") (pin "2") (pintype "passive"))
      (node (ref "D200") (pin "2") (pinfunction "2_2") (pintype "passive"))
      (node (ref "D201") (pin "2") (pinfunction "2_2") (pintype "passive"))
      (node (ref "D202") (pin "1") (pinfunction "CATHODE_1") (pintype "passive"))
      (node (ref "D203") (pin "1") (pinfunction "CATHODE_1") (pintype "passive"))
      (node (ref "D204") (pin "1") (pinfunction "CATHODE_1") (pintype "passive"))
      (node (ref "D205") (pin "1") (pinfunction "CATHODE_1") (pintype "passive"))
      (node (ref "D206") (pin "1") (pinfunction "CATHODE_1") (pintype "passive"))
      (node (ref "D207") (pin "1") (pinfunction "CATHODE_1") (pintype "passive"))
      (node (ref "D208") (pin "1") (pinfunction "A2_1") (pintype "passive"))
      (node (ref "D208") (pin "2") (pinfunction "C3_2") (pintype "passive"))
      (node (ref "D208") (pin "3") (pinfunction "A3_3") (pintype "passive"))
      (node (ref "J200") (pin "2") (pinfunction "2_2") (pintype "passive"))
      (node (ref "J201") (pin "10") (pinfunction "10_10") (pintype "passive"))
      (node (ref "J201") (pin "11") (pinfunction "11_11") (pintype "passive"))
      (node (ref "J201") (pin "12") (pinfunction "12_12") (pintype "passive"))
      (node (ref "J201") (pin "9") (pinfunction "9_9") (pintype "passive"))
      (node (ref "J202") (pin "3") (pinfunction "3_3") (pintype "passive"))
      (node (ref "J203") (pin "5") (pinfunction "GND_5") (pintype "power_in"))
      (node (ref "R201") (pin "2") (pinfunction "2_2") (pintype "passive"))
      (node (ref "R223") (pin "2") (pinfunction "2_2") (pintype "passive"))
      (node (ref "R225") (pin "1") (pintype "passive"))
      (node (ref "R227") (pin "2") (pinfunction "2_2") (pintype "passive"))
      (node (ref "U200") (pin "1") (pinfunction "GND_1") (pintype "power_in"))
      (node (ref "U200") (pin "15") (pinfunction "GND_15") (pintype "power_in"))
      (node (ref "U200") (pin "38") (pinfunction "GND_38") (pintype "power_in"))
      (node (ref "U201") (pin "29") (pinfunction "PGND_29") (pintype "passive"))
      (node (ref "U201") (pin "3") (pinfunction "GND_3") (pintype "power_in"))
      (node (ref "U202") (pin "4") (pinfunction "GND_4") (pintype "power_in"))
    )
    (net (code "43") (name "Net-(B200-Pad2)") (class "Default")
      (node (ref "B200") (pin "2") (pinfunction "2_2") (pintype "passive"))
      (node (ref "C208") (pin "1") (pintype "passive"))
    )
    (net (code "44") (name "Net-(C200-Pad1)") (class "Default")
      (node (ref "C200") (pin "1") (pintype "passive"))
      (node (ref "D201") (pin "1") (pinfunction "1_1") (pintype "passive"))
      (node (ref "J201") (pin "4") (pinfunction "4_4") (pintype "passive"))
      (node (ref "R202") (pin "2") (pinfunction "2_2") (pintype "passive"))
    )
    (net (code "45") (name "Net-(D202-ANODE)") (class "Default")
      (node (ref "D202") (pin "2") (pinfunction "ANODE_2") (pintype "passive"))
      (node (ref "R206") (pin "1") (pinfunction "1_1") (pintype "passive"))
      (node (ref "R212") (pin "1") (pintype "passive"))
      (node (ref "TP200") (pin "1") (pintype "passive"))
    )
    (net (code "46") (name "Net-(D205-ANODE)") (class "Default")
      (node (ref "D205") (pin "2") (pinfunction "ANODE_2") (pintype "passive"))
      (node (ref "R209") (pin "1") (pinfunction "1_1") (pintype "passive"))
      (node (ref "R218") (pin "1") (pintype "passive"))
      (node (ref "R223") (pin "1") (pinfunction "1_1") (pintype "passive"))
      (node (ref "TP203") (pin "1") (pintype "passive"))
    )
    (net (code "47") (name "Net-(D208-C1-Pad4)") (class "Default")
      (node (ref "D208") (pin "4") (pinfunction "C1_4") (pintype "passive"))
      (node (ref "R215") (pin "2") (pintype "passive"))
    )
    (net (code "48") (name "Net-(D208-C1-Pad5)") (class "Default")
      (node (ref "D208") (pin "5") (pinfunction "C1_5") (pintype "passive"))
      (node (ref "R216") (pin "2") (pintype "passive"))
    )
    (net (code "49") (name "Net-(D208-C1-Pad6)") (class "Default")
      (node (ref "D208") (pin "6") (pinfunction "C1_6") (pintype "passive"))
      (node (ref "R217") (pin "2") (pintype "passive"))
    )
    (net (code "50") (name "Net-(J201-Pad1)") (class "Default")
      (node (ref "J201") (pin "1") (pinfunction "1_1") (pintype "passive"))
      (node (ref "R211") (pin "2") (pinfunction "2_2") (pintype "passive"))
    )
    (net (code "51") (name "Net-(J201-Pad2)") (class "Default")
      (node (ref "J201") (pin "2") (pinfunction "2_2") (pintype "passive"))
      (node (ref "R210") (pin "2") (pinfunction "2_2") (pintype "passive"))
    )
    (net (code "52") (name "Net-(J201-Pad3)") (class "Default")
      (node (ref "J201") (pin "3") (pinfunction "3_3") (pintype "passive"))
      (node (ref "R209") (pin "2") (pinfunction "2_2") (pintype "passive"))
    )
    (net (code "53") (name "Net-(J201-Pad5)") (class "Default")
      (node (ref "J201") (pin "5") (pinfunction "5_5") (pintype "passive"))
      (node (ref "R208") (pin "2") (pinfunction "2_2") (pintype "passive"))
    )
    (net (code "54") (name "Net-(J201-Pad6)") (class "Default")
      (node (ref "J201") (pin "6") (pinfunction "6_6") (pintype "passive"))
      (node (ref "R201") (pin "1") (pinfunction "1_1") (pintype "passive"))
    )
    (net (code "55") (name "Net-(J201-Pad7)") (class "Default")
      (node (ref "J201") (pin "7") (pinfunction "7_7") (pintype "passive"))
      (node (ref "R207") (pin "2") (pinfunction "2_2") (pintype "passive"))
    )
    (net (code "56") (name "Net-(J201-Pad8)") (class "Default")
      (node (ref "J201") (pin "8") (pinfunction "8_8") (pintype "passive"))
      (node (ref "R206") (pin "2") (pinfunction "2_2") (pintype "passive"))
    )
    (net (code "57") (name "Net-(Q200-B)") (class "Default")
      (node (ref "Q200") (pin "1") (pinfunction "B_1") (pintype "passive"))
      (node (ref "R228") (pin "1") (pinfunction "1_1") (pintype "passive"))
    )
    (net (code "58") (name "Net-(Q201-B)") (class "Default")
      (node (ref "Q201") (pin "1") (pinfunction "B_1") (pintype "passive"))
      (node (ref "R229") (pin "1") (pinfunction "1_1") (pintype "passive"))
    )
    (net (code "59") (name "Net-(U200-SENSOR_VN)") (class "Default")
      (node (ref "TP209") (pin "1") (pintype "passive"))
      (node (ref "U200") (pin "5") (pinfunction "SENSOR_VN_5") (pintype "passive"))
    )
    (net (code "60") (name "Net-(U200-SENSOR_VP)") (class "Default")
      (node (ref "TP208") (pin "1") (pintype "passive"))
      (node (ref "U200") (pin "4") (pinfunction "SENSOR_VP_4") (pintype "passive"))
    )
    (net (code "61") (name "Net-(U201-VBUS)") (class "Default")
      (node (ref "R224") (pin "2") (pintype "passive"))
      (node (ref "R225") (pin "2") (pintype "passive"))
      (node (ref "U201") (pin "8") (pinfunction "VBUS_8") (pintype "passive"))
    )
    (net (code "62") (name "Net-(U201-~{RST})") (class "Default")
      (node (ref "R226") (pin "2") (pintype "passive"))
      (node (ref "U201") (pin "9") (pinfunction "~{RST}_9") (pintype "passive"))
    )
    (net (code "63") (name "Net-(U201-~{SUSPEND})") (class "Default")
      (node (ref "R227") (pin "1") (pinfunction "1_1") (pintype "passive"))
      (node (ref "U201") (pin "11") (pinfunction "~{SUSPEND}_11") (pintype "passive"))
    )
    (net (code "64") (name "V_USB") (class "Default")
      (node (ref "C207") (pin "2") (pintype "passive"))
      (node (ref "C209") (pin "1") (pintype "passive"))
      (node (ref "J203") (pin "1") (pinfunction "VCC_1") (pintype "power_in"))
      (node (ref "R224") (pin "1") (pintype "passive"))
      (node (ref "U202") (pin "6") (pinfunction "VBUS_6") (pintype "passive"))
    )
    (net (code "65") (name "unconnected-(B200-Pad4)") (class "Default")
      (node (ref "B200") (pin "4") (pinfunction "4_4") (pintype "passive"))
    )
    (net (code "66") (name "unconnected-(B201-Pad2)") (class "Default")
      (node (ref "B201") (pin "2") (pinfunction "2_2") (pintype "passive"))
    )
    (net (code "67") (name "unconnected-(B201-Pad4)") (class "Default")
      (node (ref "B201") (pin "4") (pinfunction "4_4") (pintype "passive"))
    )
    (net (code "68") (name "unconnected-(J203-ID-Pad4)") (class "Default")
      (node (ref "J203") (pin "4") (pinfunction "ID_4") (pintype "passive+no_connect"))
    )
    (net (code "69") (name "unconnected-(R215-Pad1)") (class "Default")
      (node (ref "R215") (pin "1") (pintype "passive+no_connect"))
    )
    (net (code "70") (name "unconnected-(U200-NC-Pad32)") (class "Default")
      (node (ref "U200") (pin "32") (pinfunction "NC_32") (pintype "passive+no_connect"))
    )
    (net (code "71") (name "unconnected-(U200-SCK{slash}CLK-Pad20)") (class "Default")
      (node (ref "U200") (pin "20") (pinfunction "SCK/CLK_20") (pintype "bidirectional+no_connect"))
    )
    (net (code "72") (name "unconnected-(U200-SCS{slash}CMD-Pad19)") (class "Default")
      (node (ref "U200") (pin "19") (pinfunction "SCS/CMD_19") (pintype "bidirectional+no_connect"))
    )
    (net (code "73") (name "unconnected-(U200-SDI{slash}SD1-Pad22)") (class "Default")
      (node (ref "U200") (pin "22") (pinfunction "SDI/SD1_22") (pintype "bidirectional+no_connect"))
    )
    (net (code "74") (name "unconnected-(U200-SDO{slash}SD0-Pad21)") (class "Default")
      (node (ref "U200") (pin "21") (pinfunction "SDO/SD0_21") (pintype "bidirectional+no_connect"))
    )
    (net (code "75") (name "unconnected-(U200-SHD{slash}SD2-Pad17)") (class "Default")
      (node (ref "U200") (pin "17") (pinfunction "SHD/SD2_17") (pintype "bidirectional+no_connect"))
    )
    (net (code "76") (name "unconnected-(U200-SWP{slash}SD3-Pad18)") (class "Default")
      (node (ref "U200") (pin "18") (pinfunction "SWP/SD3_18") (pintype "bidirectional+no_connect"))
    )
    (net (code "77") (name "unconnected-(U201-CHR0-Pad15)") (class "Default")
      (node (ref "U201") (pin "15") (pinfunction "CHR0_15") (pintype "passive+no_connect"))
    )
    (net (code "78") (name "unconnected-(U201-CHR1-Pad14)") (class "Default")
      (node (ref "U201") (pin "14") (pinfunction "CHR1_14") (pintype "passive+no_connect"))
    )
    (net (code "79") (name "unconnected-(U201-CHREN-Pad13)") (class "Default")
      (node (ref "U201") (pin "13") (pinfunction "CHREN_13") (pintype "passive+no_connect"))
    )
    (net (code "80") (name "unconnected-(U201-IO0-Pad19)") (class "Default")
      (node (ref "U201") (pin "19") (pinfunction "IO0_19") (pintype "passive+no_connect"))
    )
    (net (code "81") (name "unconnected-(U201-IO1-Pad18)") (class "Default")
      (node (ref "U201") (pin "18") (pinfunction "IO1_18") (pintype "passive+no_connect"))
    )
    (net (code "82") (name "unconnected-(U201-IO2-Pad17)") (class "Default")
      (node (ref "U201") (pin "17") (pinfunction "IO2_17") (pintype "passive+no_connect"))
    )
    (net (code "83") (name "unconnected-(U201-IO3-Pad16)") (class "Default")
      (node (ref "U201") (pin "16") (pinfunction "IO3_16") (pintype "passive+no_connect"))
    )
    (net (code "84") (name "unconnected-(U201-IO4-Pad22)") (class "Default")
      (node (ref "U201") (pin "22") (pinfunction "IO4_22") (pintype "passive+no_connect"))
    )
    (net (code "85") (name "unconnected-(U201-IO5-Pad21)") (class "Default")
      (node (ref "U201") (pin "21") (pinfunction "IO5_21") (pintype "passive+no_connect"))
    )
    (net (code "86") (name "unconnected-(U201-IO6-Pad20)") (class "Default")
      (node (ref "U201") (pin "20") (pinfunction "IO6_20") (pintype "passive+no_connect"))
    )
    (net (code "87") (name "unconnected-(U201-NC-Pad10)") (class "Default")
      (node (ref "U201") (pin "10") (pinfunction "NC_10") (pintype "passive+no_connect"))
    )
    (net (code "88") (name "unconnected-(U201-SUSPEND-Pad12)") (class "Default")
      (node (ref "U201") (pin "12") (pinfunction "SUSPEND_12") (pintype "passive+no_connect"))
    )
    (net (code "89") (name "unconnected-(U202-ID-Pad3)") (class "Default")
      (node (ref "U202") (pin "3") (pinfunction "ID_3") (pintype "passive"))
    )
    (net (code "90") (name "unconnected-(U202-NC-Pad5)") (class "Default")
      (node (ref "U202") (pin "5") (pinfunction "NC_5") (pintype "passive"))
    )
  )
)
